# CM_MOTOR.net
KiCad netlist of a schematic drawn in Altium Designer
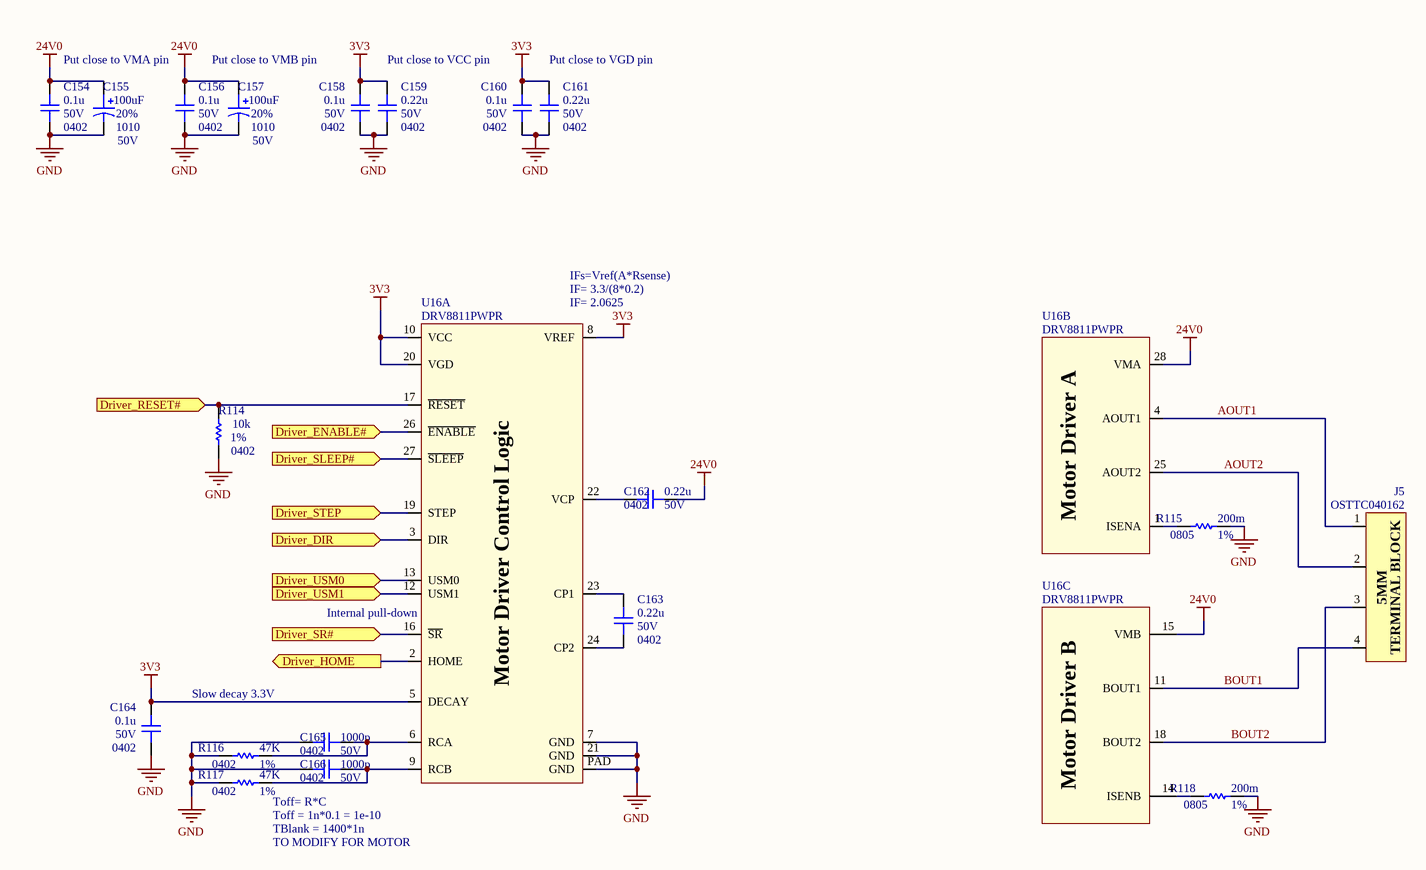
[diagram p0: CM_MOTOR.SchDoc]

(export (version "E")
  (design (tool "Eeschema 10.0.6"))
  (components
    (comp (ref "C154")
      (value "0.1u")
      (footprint "CAP_0402")
      (description "CAP - 0402")
      (fields
        (field (name "VOLTAGE") "50V")
        (field (name "PACKAGE") "0402")
        (field (name "CREATEDBY") "Jonathan Bouchard")
      )
      (libsource (lib "S7CAS_Lib2019_REV1_00") (part "CAP - 0402"))
    )
    (comp (ref "C155")
      (value "100uF")
      (footprint "CAP_ALU_1010_vishay")
      (description "CAP - ALU 100uF 20% 50V - 1010")
      (fields
        (field (name "MFG") "Vishay Dale")
        (field (name "MFG PART NUMBER") "MAL215099101E3")
        (field (name "VOLTAGE") "50V")
        (field (name "PACKAGE") "1010")
        (field (name "PRECISION") "20%")
        (field (name "CREATEDBY") "Jonathan Bouchard")
      )
      (libsource (lib "S7CAS_Lib2019_REV1_00") (part "CAP_ALU_MAL215099101E3"))
    )
    (comp (ref "C156")
      (value "0.1u")
      (footprint "CAP_0402")
      (description "CAP - 0402")
      (fields
        (field (name "VOLTAGE") "50V")
        (field (name "PACKAGE") "0402")
        (field (name "CREATEDBY") "Jonathan Bouchard")
      )
      (libsource (lib "S7CAS_Lib2019_REV1_00") (part "CAP - 0402"))
    )
    (comp (ref "C157")
      (value "100uF")
      (footprint "CAP_ALU_1010_vishay")
      (description "CAP - ALU 100uF 20% 50V - 1010")
      (fields
        (field (name "MFG") "Vishay Dale")
        (field (name "MFG PART NUMBER") "MAL215099101E3")
        (field (name "VOLTAGE") "50V")
        (field (name "PACKAGE") "1010")
        (field (name "PRECISION") "20%")
        (field (name "CREATEDBY") "Jonathan Bouchard")
      )
      (libsource (lib "S7CAS_Lib2019_REV1_00") (part "CAP_ALU_MAL215099101E3"))
    )
    (comp (ref "C158")
      (value "0.1u")
      (footprint "CAP_0402")
      (description "CAP - 0402")
      (fields
        (field (name "VOLTAGE") "50V")
        (field (name "PACKAGE") "0402")
        (field (name "CREATEDBY") "Jonathan Bouchard")
      )
      (libsource (lib "S7CAS_Lib2019_REV1_00") (part "CAP - 0402"))
    )
    (comp (ref "C159")
      (value "0.22u")
      (footprint "CAP_0402")
      (description "CAP - 0402")
      (fields
        (field (name "VOLTAGE") "50V")
        (field (name "PACKAGE") "0402")
        (field (name "CREATEDBY") "Jonathan Bouchard")
      )
      (libsource (lib "S7CAS_Lib2019_REV1_00") (part "CAP - 0402"))
    )
    (comp (ref "C160")
      (value "0.1u")
      (footprint "CAP_0402")
      (description "CAP - 0402")
      (fields
        (field (name "VOLTAGE") "50V")
        (field (name "PACKAGE") "0402")
        (field (name "CREATEDBY") "Jonathan Bouchard")
      )
      (libsource (lib "S7CAS_Lib2019_REV1_00") (part "CAP - 0402"))
    )
    (comp (ref "C161")
      (value "0.22u")
      (footprint "CAP_0402")
      (description "CAP - 0402")
      (fields
        (field (name "VOLTAGE") "50V")
        (field (name "PACKAGE") "0402")
        (field (name "CREATEDBY") "Jonathan Bouchard")
      )
      (libsource (lib "S7CAS_Lib2019_REV1_00") (part "CAP - 0402"))
    )
    (comp (ref "C162")
      (value "0.22u")
      (footprint "CAP_0402")
      (description "CAP - 0402")
      (fields
        (field (name "VOLTAGE") "50V")
        (field (name "PACKAGE") "0402")
        (field (name "CREATEDBY") "Jonathan Bouchard")
      )
      (libsource (lib "S7CAS_Lib2019_REV1_00") (part "CAP - 0402"))
    )
    (comp (ref "C163")
      (value "0.22u")
      (footprint "CAP_0402")
      (description "CAP - 0402")
      (fields
        (field (name "VOLTAGE") "50V")
        (field (name "PACKAGE") "0402")
        (field (name "CREATEDBY") "Jonathan Bouchard")
      )
      (libsource (lib "S7CAS_Lib2019_REV1_00") (part "CAP - 0402"))
    )
    (comp (ref "C164")
      (value "0.1u")
      (footprint "CAP_0402")
      (description "CAP - 0402")
      (fields
        (field (name "VOLTAGE") "50V")
        (field (name "PACKAGE") "0402")
        (field (name "CREATEDBY") "Jonathan Bouchard")
      )
      (libsource (lib "S7CAS_Lib2019_REV1_00") (part "CAP - 0402"))
    )
    (comp (ref "C165")
      (value "1000p")
      (footprint "CAP_0402")
      (description "CAP - 0402")
      (fields
        (field (name "VOLTAGE") "50V")
        (field (name "PACKAGE") "0402")
        (field (name "CREATEDBY") "Jonathan Bouchard")
      )
      (libsource (lib "S7CAS_Lib2019_REV1_00") (part "CAP - 0402"))
    )
    (comp (ref "C166")
      (value "1000p")
      (footprint "CAP_0402")
      (description "CAP - 0402")
      (fields
        (field (name "VOLTAGE") "50V")
        (field (name "PACKAGE") "0402")
        (field (name "CREATEDBY") "Jonathan Bouchard")
      )
      (libsource (lib "S7CAS_Lib2019_REV1_00") (part "CAP - 0402"))
    )
    (comp (ref "J5")
      (value "OSTTC040162")
      (footprint "CONN_TERMINAL_OSTTA040161")
      (description "CONN -  TERMINAL BLOCK 4POS 5MM - TH")
      (fields (field (name "MFG") "On Shore Technology Inc.") (field (name "CREATEDBY") "Jonathan Bouchard"))
      (libsource (lib "S7CAS_Lib2019_REV1_00") (part "CONN_TERMINAL_OSTTC040162"))
    )
    (comp (ref "R114")
      (value "10k")
      (footprint "RES_0402")
      (description "RES - 0402")
      (fields
        (field (name "VOLTAGE") "50V")
        (field (name "POWER") "1/16W")
        (field (name "PACKAGE") "0402")
        (field (name "PRECISION") "1%")
        (field (name "CREATEDBY") "Jonathan Bouchard")
      )
      (libsource (lib "S7CAS_Lib2019_REV1_00") (part "RES - 0402"))
    )
    (comp (ref "R115")
      (value "200m")
      (footprint "RES_0402")
      (description "RES - 0402")
      (fields
        (field (name "VOLTAGE") "50V")
        (field (name "POWER") "1/16W")
        (field (name "PACKAGE") "0805")
        (field (name "PRECISION") "1%")
        (field (name "CREATEDBY") "Jonathan Bouchard")
      )
      (libsource (lib "S7CAS_Lib2019_REV1_00") (part "RES - 0402"))
    )
    (comp (ref "R116")
      (value "47K")
      (footprint "RES_0402")
      (description "RES - 0402")
      (fields
        (field (name "VOLTAGE") "50V")
        (field (name "POWER") "1/16W")
        (field (name "PACKAGE") "0402")
        (field (name "PRECISION") "1%")
        (field (name "CREATEDBY") "Jonathan Bouchard")
      )
      (libsource (lib "S7CAS_Lib2019_REV1_00") (part "RES - 0402"))
    )
    (comp (ref "R117")
      (value "47K")
      (footprint "RES_0402")
      (description "RES - 0402")
      (fields
        (field (name "VOLTAGE") "50V")
        (field (name "POWER") "1/16W")
        (field (name "PACKAGE") "0402")
        (field (name "PRECISION") "1%")
        (field (name "CREATEDBY") "Jonathan Bouchard")
      )
      (libsource (lib "S7CAS_Lib2019_REV1_00") (part "RES - 0402"))
    )
    (comp (ref "R118")
      (value "200m")
      (footprint "RES_0402")
      (description "RES - 0402")
      (fields
        (field (name "VOLTAGE") "50V")
        (field (name "POWER") "1/16W")
        (field (name "PACKAGE") "0805")
        (field (name "PRECISION") "1%")
        (field (name "CREATEDBY") "Jonathan Bouchard")
      )
      (libsource (lib "S7CAS_Lib2019_REV1_00") (part "RES - 0402"))
    )
    (comp (ref "U16")
      (value "DRV8811PWPR")
      (footprint "POW_MOTOR_DRV8811PWPR")
      (description "POW - STEPPER MOTOR DRIVER - SOP-28")
      (fields
        (field (name "VOLTAGE") "3 V ~ 5.5 V / 8 V ~ 38 V")
        (field (name "MFG") "Texas Instrument")
        (field (name "CREATEDBY") "Jonathan Bouchard")
      )
      (libsource (lib "S7CAS_Lib2019_REV1_00") (part "POW_MOTOR_DRV8811PWPR"))
    )
  )
  (nets
    (net (code "2") (name "/AOUT1") (class "Default")
      (node (ref "J5") (pin "1") (pinfunction "1_1") (pintype "passive"))
      (node (ref "U16") (pin "4") (pinfunction "AOUT1_4") (pintype "passive"))
    )
    (net (code "3") (name "/AOUT2") (class "Default")
      (node (ref "J5") (pin "2") (pinfunction "2_2") (pintype "passive"))
      (node (ref "U16") (pin "25") (pinfunction "AOUT2_25") (pintype "passive"))
    )
    (net (code "4") (name "/BOUT1") (class "Default")
      (node (ref "J5") (pin "4") (pinfunction "4_4") (pintype "passive"))
      (node (ref "U16") (pin "11") (pinfunction "BOUT1_11") (pintype "passive"))
    )
    (net (code "5") (name "/BOUT2") (class "Default")
      (node (ref "J5") (pin "3") (pinfunction "3_3") (pintype "passive"))
      (node (ref "U16") (pin "18") (pinfunction "BOUT2_18") (pintype "passive"))
    )
    (net (code "6") (name "/Driver_DIR") (class "Default")
      (node (ref "U16") (pin "3") (pinfunction "DIR_3") (pintype "passive"))
    )
    (net (code "7") (name "/Driver_ENABLE#") (class "Default")
      (node (ref "U16") (pin "26") (pinfunction "~{ENABLE}_26") (pintype "passive"))
    )
    (net (code "8") (name "/Driver_HOME") (class "Default")
      (node (ref "U16") (pin "2") (pinfunction "HOME_2") (pintype "passive"))
    )
    (net (code "9") (name "/Driver_RESET#") (class "Default")
      (node (ref "R114") (pin "2") (pinfunction "2_2") (pintype "passive"))
      (node (ref "U16") (pin "17") (pinfunction "~{RESET}_17") (pintype "passive"))
    )
    (net (code "10") (name "/Driver_SLEEP#") (class "Default")
      (node (ref "U16") (pin "27") (pinfunction "~{SLEEP}_27") (pintype "passive"))
    )
    (net (code "11") (name "/Driver_SR#") (class "Default")
      (node (ref "U16") (pin "16") (pinfunction "~{SR}_16") (pintype "passive"))
    )
    (net (code "12") (name "/Driver_STEP") (class "Default")
      (node (ref "U16") (pin "19") (pinfunction "STEP_19") (pintype "passive"))
    )
    (net (code "13") (name "/Driver_USM0") (class "Default")
      (node (ref "U16") (pin "13") (pinfunction "USM0_13") (pintype "passive"))
    )
    (net (code "14") (name "/Driver_USM1") (class "Default")
      (node (ref "U16") (pin "12") (pinfunction "USM1_12") (pintype "passive"))
    )
    (net (code "15") (name "3V3") (class "Default")
      (node (ref "C158") (pin "2") (pinfunction "2_2") (pintype "passive"))
      (node (ref "C159") (pin "2") (pinfunction "2_2") (pintype "passive"))
      (node (ref "C160") (pin "2") (pinfunction "2_2") (pintype "passive"))
      (node (ref "C161") (pin "2") (pinfunction "2_2") (pintype "passive"))
      (node (ref "C164") (pin "2") (pinfunction "2_2") (pintype "passive"))
      (node (ref "U16") (pin "10") (pinfunction "VCC_10") (pintype "passive"))
      (node (ref "U16") (pin "20") (pinfunction "VGD_20") (pintype "passive"))
      (node (ref "U16") (pin "5") (pinfunction "DECAY_5") (pintype "passive"))
      (node (ref "U16") (pin "8") (pinfunction "VREF_8") (pintype "passive"))
    )
    (net (code "16") (name "24V0") (class "Default")
      (node (ref "C154") (pin "2") (pinfunction "2_2") (pintype "passive"))
      (node (ref "C155") (pin "1") (pinfunction "1_1") (pintype "passive"))
      (node (ref "C156") (pin "2") (pinfunction "2_2") (pintype "passive"))
      (node (ref "C157") (pin "1") (pinfunction "1_1") (pintype "passive"))
      (node (ref "C162") (pin "2") (pinfunction "2_2") (pintype "passive"))
      (node (ref "U16") (pin "15") (pinfunction "VMB_15") (pintype "passive"))
      (node (ref "U16") (pin "28") (pinfunction "VMA_28") (pintype "passive"))
    )
    (net (code "17") (name "GND") (class "Default")
      (node (ref "C154") (pin "1") (pinfunction "1_1") (pintype "passive"))
      (node (ref "C155") (pin "2") (pinfunction "2_2") (pintype "passive"))
      (node (ref "C156") (pin "1") (pinfunction "1_1") (pintype "passive"))
      (node (ref "C157") (pin "2") (pinfunction "2_2") (pintype "passive"))
      (node (ref "C158") (pin "1") (pinfunction "1_1") (pintype "passive"))
      (node (ref "C159") (pin "1") (pinfunction "1_1") (pintype "passive"))
      (node (ref "C160") (pin "1") (pinfunction "1_1") (pintype "passive"))
      (node (ref "C161") (pin "1") (pinfunction "1_1") (pintype "passive"))
      (node (ref "C164") (pin "1") (pinfunction "1_1") (pintype "passive"))
      (node (ref "C165") (pin "2") (pinfunction "2_2") (pintype "passive"))
      (node (ref "C166") (pin "2") (pinfunction "2_2") (pintype "passive"))
      (node (ref "R114") (pin "1") (pinfunction "1_1") (pintype "passive"))
      (node (ref "R115") (pin "2") (pinfunction "2_2") (pintype "passive"))
      (node (ref "R116") (pin "1") (pinfunction "1_1") (pintype "passive"))
      (node (ref "R117") (pin "1") (pinfunction "1_1") (pintype "passive"))
      (node (ref "R118") (pin "2") (pinfunction "2_2") (pintype "passive"))
      (node (ref "U16") (pin "21") (pinfunction "GND_21") (pintype "passive"))
      (node (ref "U16") (pin "7") (pinfunction "GND_7") (pintype "passive"))
      (node (ref "U16") (pin "PAD") (pinfunction "GND_PAD") (pintype "passive"))
    )
    (net (code "18") (name "Net-(U16A-CP1)") (class "Default")
      (node (ref "C163") (pin "2") (pinfunction "2_2") (pintype "passive"))
      (node (ref "U16") (pin "23") (pinfunction "CP1_23") (pintype "passive"))
    )
    (net (code "19") (name "Net-(U16A-CP2)") (class "Default")
      (node (ref "C163") (pin "1") (pinfunction "1_1") (pintype "passive"))
      (node (ref "U16") (pin "24") (pinfunction "CP2_24") (pintype "passive"))
    )
    (net (code "20") (name "Net-(U16A-RCA)") (class "Default")
      (node (ref "C165") (pin "1") (pinfunction "1_1") (pintype "passive"))
      (node (ref "R116") (pin "2") (pinfunction "2_2") (pintype "passive"))
      (node (ref "U16") (pin "6") (pinfunction "RCA_6") (pintype "passive"))
    )
    (net (code "21") (name "Net-(U16A-RCB)") (class "Default")
      (node (ref "C166") (pin "1") (pinfunction "1_1") (pintype "passive"))
      (node (ref "R117") (pin "2") (pinfunction "2_2") (pintype "passive"))
      (node (ref "U16") (pin "9") (pinfunction "RCB_9") (pintype "passive"))
    )
    (net (code "22") (name "Net-(U16A-VCP)") (class "Default")
      (node (ref "C162") (pin "1") (pinfunction "1_1") (pintype "passive"))
      (node (ref "U16") (pin "22") (pinfunction "VCP_22") (pintype "passive"))
    )
    (net (code "23") (name "Net-(U16B-ISENA)") (class "Default")
      (node (ref "R115") (pin "1") (pinfunction "1_1") (pintype "passive"))
      (node (ref "U16") (pin "1") (pinfunction "ISENA_1") (pintype "passive"))
    )
    (net (code "24") (name "Net-(U16C-ISENB)") (class "Default")
      (node (ref "R118") (pin "1") (pinfunction "1_1") (pintype "passive"))
      (node (ref "U16") (pin "14") (pinfunction "ISENB_14") (pintype "passive"))
    )
  )
)
